# Nusbio_Test_GPIOS_Extension.net
KiCad netlist of a schematic drawn in EAGLE
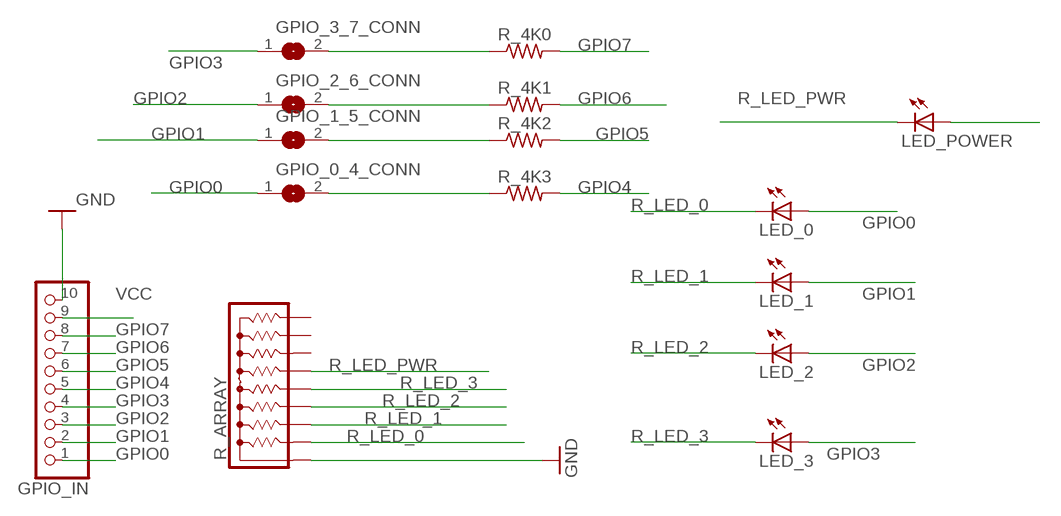
[diagram p0: schematic, sheet 1]

(export (version "E")
  (design (tool "Eeschema 10.0.6"))
  (components
    (comp (ref "GPIO_0_4_CONN")
      (value "SOLDERJUMPERREFLOW")
      (footprint "eagle-import:SOLDERJUMPER_REFLOW")
      (libsource (lib "eagle-import") (part "SOLDERJUMPERREFLOW"))
    )
    (comp (ref "GPIO_1_5_CONN")
      (value "SOLDERJUMPERREFLOW")
      (footprint "eagle-import:SOLDERJUMPER_REFLOW")
      (libsource (lib "eagle-import") (part "SOLDERJUMPERREFLOW"))
    )
    (comp (ref "GPIO_2_6_CONN")
      (value "SOLDERJUMPERREFLOW")
      (footprint "eagle-import:SOLDERJUMPER_REFLOW")
      (libsource (lib "eagle-import") (part "SOLDERJUMPERREFLOW"))
    )
    (comp (ref "GPIO_3_7_CONN")
      (value "SOLDERJUMPERREFLOW")
      (footprint "eagle-import:SOLDERJUMPER_REFLOW")
      (libsource (lib "eagle-import") (part "SOLDERJUMPERREFLOW"))
    )
    (comp (ref "GPIO_IN")
      (value "PINHD-1X10")
      (footprint "eagle-import:1X10-BIG")
      (libsource (lib "eagle-import") (part "PINHD-1X10"))
    )
    (comp (ref "LED_0")
      (value "LEDSMT1206")
      (footprint "eagle-import:1206")
      (libsource (lib "eagle-import") (part "LEDSMT1206"))
    )
    (comp (ref "LED_1")
      (value "LEDSMT1206")
      (footprint "eagle-import:1206")
      (libsource (lib "eagle-import") (part "LEDSMT1206"))
    )
    (comp (ref "LED_2")
      (value "LEDSMT1206")
      (footprint "eagle-import:1206")
      (libsource (lib "eagle-import") (part "LEDSMT1206"))
    )
    (comp (ref "LED_3")
      (value "LEDSMT1206")
      (footprint "eagle-import:1206")
      (libsource (lib "eagle-import") (part "LEDSMT1206"))
    )
    (comp (ref "LED_POWER")
      (value "LEDSMT1206")
      (footprint "eagle-import:1206")
      (libsource (lib "eagle-import") (part "LEDSMT1206"))
    )
    (comp (ref "R_4K0")
      (value "R-US_R1206")
      (footprint "eagle-import:R1206")
      (libsource (lib "eagle-import") (part "R-US_R1206"))
    )
    (comp (ref "R_4K1")
      (value "R-US_R1206")
      (footprint "eagle-import:R1206")
      (libsource (lib "eagle-import") (part "R-US_R1206"))
    )
    (comp (ref "R_4K2")
      (value "R-US_R1206")
      (footprint "eagle-import:R1206")
      (libsource (lib "eagle-import") (part "R-US_R1206"))
    )
    (comp (ref "R_4K3")
      (value "R-US_R1206")
      (footprint "eagle-import:R1206")
      (libsource (lib "eagle-import") (part "R-US_R1206"))
    )
    (comp (ref "R_ARRAY")
      (value "4609X")
      (footprint "eagle-import:SIP9")
      (libsource (lib "eagle-import") (part "4609X"))
    )
  )
  (nets
    (net (code "1") (name "/GPIO0") (class "Default")
      (node (ref "GPIO_0_4_CONN") (pin "1") (pinfunction "1_1") (pintype "passive"))
      (node (ref "GPIO_IN") (pin "1") (pinfunction "1_1") (pintype "passive"))
      (node (ref "LED_0") (pin "A") (pinfunction "A_A") (pintype "passive"))
    )
    (net (code "2") (name "/GPIO1") (class "Default")
      (node (ref "GPIO_1_5_CONN") (pin "1") (pinfunction "1_1") (pintype "passive"))
      (node (ref "GPIO_IN") (pin "2") (pinfunction "2_2") (pintype "passive"))
      (node (ref "LED_1") (pin "A") (pinfunction "A_A") (pintype "passive"))
    )
    (net (code "3") (name "/GPIO2") (class "Default")
      (node (ref "GPIO_2_6_CONN") (pin "1") (pinfunction "1_1") (pintype "passive"))
      (node (ref "GPIO_IN") (pin "3") (pinfunction "3_3") (pintype "passive"))
      (node (ref "LED_2") (pin "A") (pinfunction "A_A") (pintype "passive"))
    )
    (net (code "4") (name "/GPIO3") (class "Default")
      (node (ref "GPIO_3_7_CONN") (pin "1") (pinfunction "1_1") (pintype "passive"))
      (node (ref "GPIO_IN") (pin "4") (pinfunction "4_4") (pintype "passive"))
      (node (ref "LED_3") (pin "A") (pinfunction "A_A") (pintype "passive"))
    )
    (net (code "5") (name "/GPIO4") (class "Default")
      (node (ref "GPIO_IN") (pin "5") (pinfunction "5_5") (pintype "passive"))
      (node (ref "R_4K3") (pin "2") (pinfunction "2_2") (pintype "passive"))
    )
    (net (code "6") (name "/GPIO5") (class "Default")
      (node (ref "GPIO_IN") (pin "6") (pinfunction "6_6") (pintype "passive"))
      (node (ref "R_4K2") (pin "2") (pinfunction "2_2") (pintype "passive"))
    )
    (net (code "7") (name "/GPIO6") (class "Default")
      (node (ref "GPIO_IN") (pin "7") (pinfunction "7_7") (pintype "passive"))
      (node (ref "R_4K1") (pin "2") (pinfunction "2_2") (pintype "passive"))
    )
    (net (code "8") (name "/GPIO7") (class "Default")
      (node (ref "GPIO_IN") (pin "8") (pinfunction "8_8") (pintype "passive"))
      (node (ref "R_4K0") (pin "2") (pinfunction "2_2") (pintype "passive"))
    )
    (net (code "9") (name "/R_LED_0") (class "Default")
      (node (ref "LED_0") (pin "C") (pinfunction "C_C") (pintype "passive"))
      (node (ref "R_ARRAY") (pin "2") (pinfunction "2_2") (pintype "passive"))
    )
    (net (code "10") (name "/R_LED_1") (class "Default")
      (node (ref "LED_1") (pin "C") (pinfunction "C_C") (pintype "passive"))
      (node (ref "R_ARRAY") (pin "3") (pinfunction "3_3") (pintype "passive"))
    )
    (net (code "11") (name "/R_LED_2") (class "Default")
      (node (ref "LED_2") (pin "C") (pinfunction "C_C") (pintype "passive"))
      (node (ref "R_ARRAY") (pin "4") (pinfunction "4_4") (pintype "passive"))
    )
    (net (code "12") (name "/R_LED_3") (class "Default")
      (node (ref "LED_3") (pin "C") (pinfunction "C_C") (pintype "passive"))
      (node (ref "R_ARRAY") (pin "5") (pinfunction "5_5") (pintype "passive"))
    )
    (net (code "13") (name "/R_LED_PWR") (class "Default")
      (node (ref "LED_POWER") (pin "C") (pinfunction "C_C") (pintype "passive"))
      (node (ref "R_ARRAY") (pin "6") (pinfunction "6_6") (pintype "passive"))
    )
    (net (code "14") (name "/VCC") (class "Default")
      (node (ref "GPIO_IN") (pin "9") (pinfunction "9_9") (pintype "passive"))
      (node (ref "LED_POWER") (pin "A") (pinfunction "A_A") (pintype "passive"))
    )
    (net (code "15") (name "GND") (class "Default")
      (node (ref "GPIO_IN") (pin "10") (pinfunction "10_10") (pintype "passive"))
      (node (ref "R_ARRAY") (pin "1") (pinfunction "1_1") (pintype "passive"))
    )
    (net (code "16") (name "Net-(GPIO_0_4_CONN-Pad2)") (class "Default")
      (node (ref "GPIO_0_4_CONN") (pin "2") (pinfunction "2_2") (pintype "passive"))
      (node (ref "R_4K3") (pin "1") (pinfunction "1_1") (pintype "passive"))
    )
    (net (code "17") (name "Net-(GPIO_1_5_CONN-Pad2)") (class "Default")
      (node (ref "GPIO_1_5_CONN") (pin "2") (pinfunction "2_2") (pintype "passive"))
      (node (ref "R_4K2") (pin "1") (pinfunction "1_1") (pintype "passive"))
    )
    (net (code "18") (name "Net-(GPIO_2_6_CONN-Pad2)") (class "Default")
      (node (ref "GPIO_2_6_CONN") (pin "2") (pinfunction "2_2") (pintype "passive"))
      (node (ref "R_4K1") (pin "1") (pinfunction "1_1") (pintype "passive"))
    )
    (net (code "19") (name "Net-(GPIO_3_7_CONN-Pad2)") (class "Default")
      (node (ref "GPIO_3_7_CONN") (pin "2") (pinfunction "2_2") (pintype "passive"))
      (node (ref "R_4K0") (pin "1") (pinfunction "1_1") (pintype "passive"))
    )
    (net (code "20") (name "unconnected-(R_ARRAY-Pad7)") (class "Default")
      (node (ref "R_ARRAY") (pin "7") (pinfunction "7_7") (pintype "passive"))
    )
    (net (code "21") (name "unconnected-(R_ARRAY-Pad8)") (class "Default")
      (node (ref "R_ARRAY") (pin "8") (pinfunction "8_8") (pintype "passive"))
    )
    (net (code "22") (name "unconnected-(R_ARRAY-Pad9)") (class "Default")
      (node (ref "R_ARRAY") (pin "9") (pinfunction "9_9") (pintype "passive"))
    )
  )
)
